# LME49830_Breakout.net
KiCad netlist of a schematic drawn in EAGLE
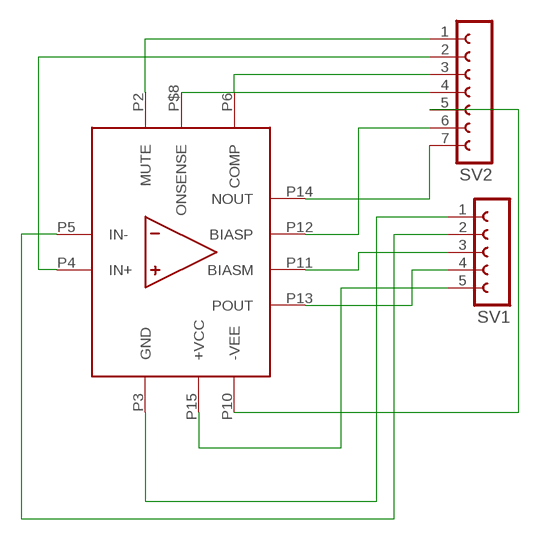
[diagram p0: schematic, sheet 1]

(export (version "E")
  (design (tool "Eeschema 10.0.6"))
  (components
    (comp (ref "SV1")
      (value "FE05-1")
      (footprint "eagle-import:FE05-1")
      (libsource (lib "eagle-import") (part "FE05-1"))
    )
    (comp (ref "SV2")
      (value "FE07-1")
      (footprint "eagle-import:FE07")
      (libsource (lib "eagle-import") (part "FE07-1"))
    )
    (comp (ref "U$1")
      (value "LME49830")
      (footprint "eagle-import:NDN0015A")
      (libsource (lib "eagle-import") (part "LME49830"))
    )
  )
  (nets
    (net (code "1") (name "Net-(U$1-+VCC)") (class "Default")
      (node (ref "SV1") (pin "5") (pinfunction "5_5") (pintype "passive"))
      (node (ref "U$1") (pin "P15") (pinfunction "+VCC_P15") (pintype "bidirectional"))
    )
    (net (code "2") (name "Net-(U$1--VEE)") (class "Default")
      (node (ref "SV2") (pin "5") (pinfunction "5_5") (pintype "passive"))
      (node (ref "U$1") (pin "P10") (pinfunction "-VEE_P10") (pintype "bidirectional"))
    )
    (net (code "3") (name "Net-(U$1-BIASM)") (class "Default")
      (node (ref "SV1") (pin "3") (pinfunction "3_3") (pintype "passive"))
      (node (ref "U$1") (pin "P11") (pinfunction "BIASM_P11") (pintype "bidirectional"))
    )
    (net (code "4") (name "Net-(U$1-BIASP)") (class "Default")
      (node (ref "SV2") (pin "6") (pinfunction "6_6") (pintype "passive"))
      (node (ref "U$1") (pin "P12") (pinfunction "BIASP_P12") (pintype "bidirectional"))
    )
    (net (code "5") (name "Net-(U$1-COMP)") (class "Default")
      (node (ref "SV2") (pin "3") (pinfunction "3_3") (pintype "passive"))
      (node (ref "U$1") (pin "P6") (pinfunction "COMP_P6") (pintype "bidirectional"))
    )
    (net (code "6") (name "Net-(U$1-GND)") (class "Default")
      (node (ref "SV1") (pin "1") (pinfunction "1_1") (pintype "passive"))
      (node (ref "U$1") (pin "P3") (pinfunction "GND_P3") (pintype "bidirectional"))
    )
    (net (code "7") (name "Net-(U$1-IN+)") (class "Default")
      (node (ref "SV2") (pin "2") (pinfunction "2_2") (pintype "passive"))
      (node (ref "U$1") (pin "P4") (pinfunction "IN+_P4") (pintype "bidirectional"))
    )
    (net (code "8") (name "Net-(U$1-IN-)") (class "Default")
      (node (ref "SV1") (pin "2") (pinfunction "2_2") (pintype "passive"))
      (node (ref "U$1") (pin "P5") (pinfunction "IN-_P5") (pintype "bidirectional"))
    )
    (net (code "9") (name "Net-(U$1-MUTE)") (class "Default")
      (node (ref "SV2") (pin "1") (pinfunction "1_1") (pintype "passive"))
      (node (ref "U$1") (pin "P2") (pinfunction "MUTE_P2") (pintype "bidirectional"))
    )
    (net (code "10") (name "Net-(U$1-NOUT)") (class "Default")
      (node (ref "SV2") (pin "7") (pinfunction "7_7") (pintype "passive"))
      (node (ref "U$1") (pin "P14") (pinfunction "NOUT_P14") (pintype "bidirectional"))
    )
    (net (code "11") (name "Net-(U$1-ONSENSE)") (class "Default")
      (node (ref "SV2") (pin "4") (pinfunction "4_4") (pintype "passive"))
      (node (ref "U$1") (pin "P$8") (pinfunction "ONSENSE_P$8") (pintype "bidirectional"))
    )
    (net (code "12") (name "Net-(U$1-POUT)") (class "Default")
      (node (ref "SV1") (pin "4") (pinfunction "4_4") (pintype "passive"))
      (node (ref "U$1") (pin "P13") (pinfunction "POUT_P13") (pintype "bidirectional"))
    )
  )
)
